# PAGE08_System_Power.net
KiCad netlist of a schematic drawn in Altium Designer
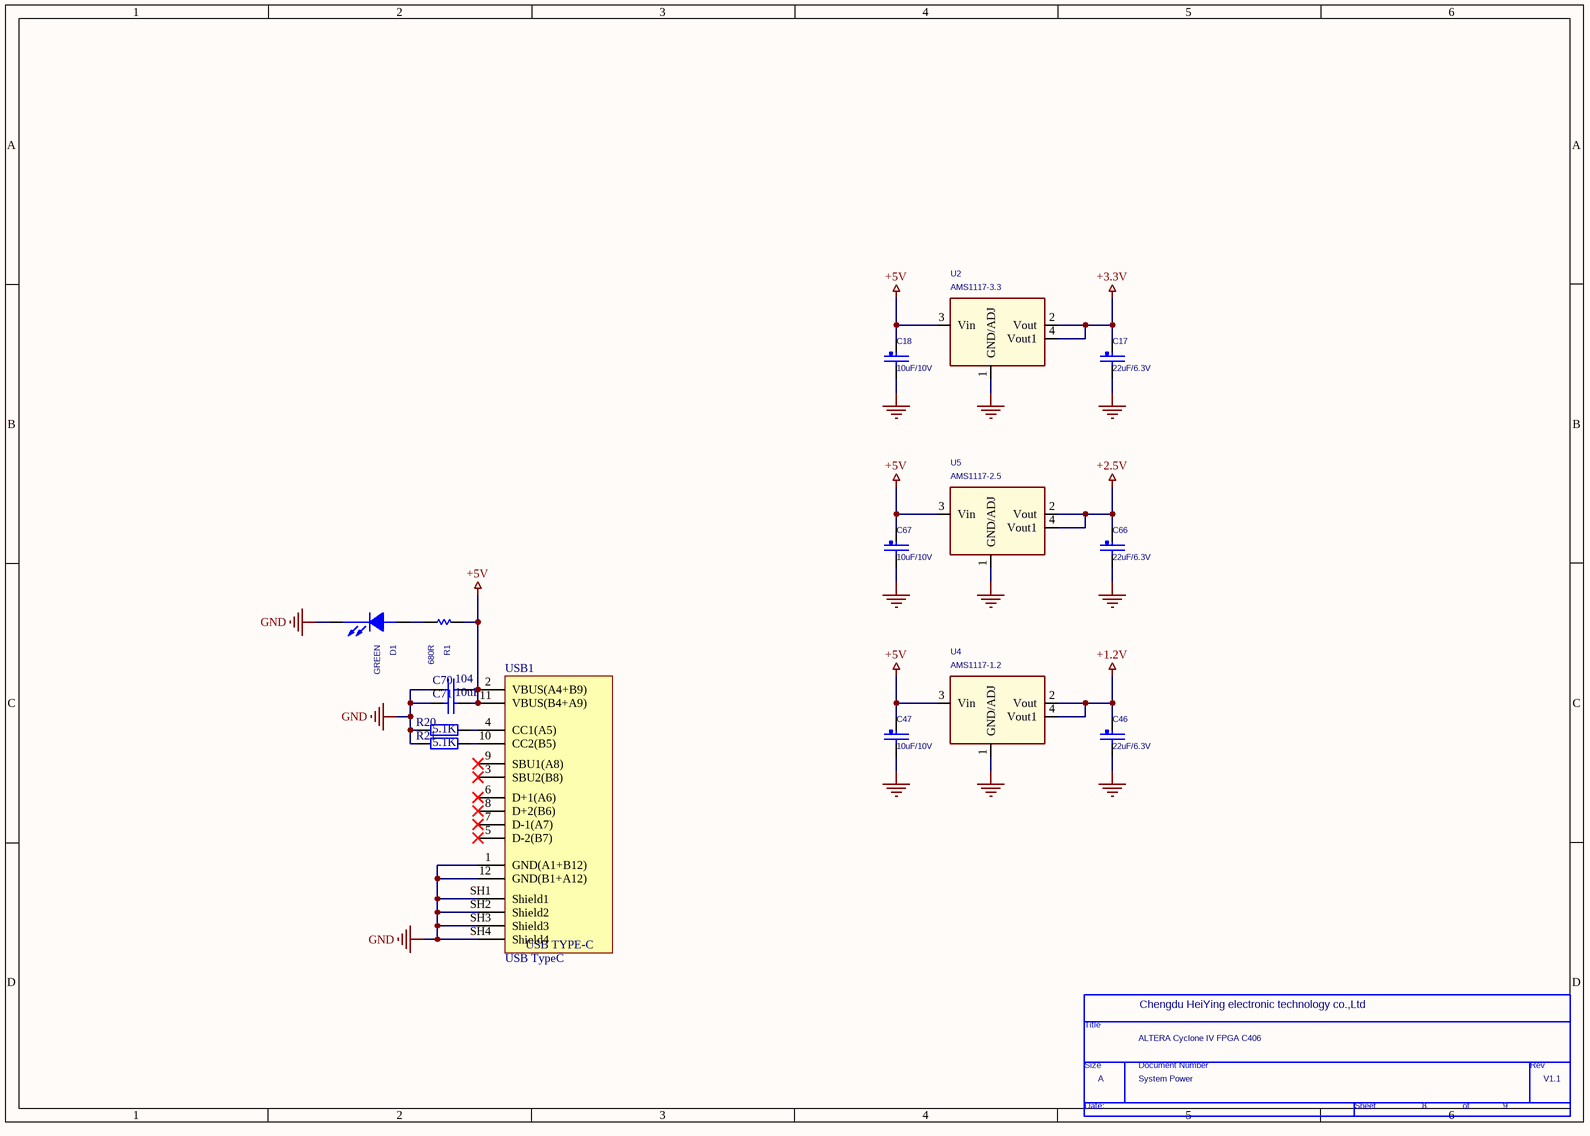
[diagram p0: PAGE08 System Power.SchDoc]

(export (version "E")
  (design (tool "Eeschema 10.0.6"))
  (components
    (comp (ref "C17")
      (value "22uF/6.3V")
      (description "Capacitor, 10u, 0805, X6S, 10%, 10V")
      (fields (field (name "TOLERANCE") "10%"))
      (libsource (lib "*") (part "CAP_NP"))
    )
    (comp (ref "C18")
      (value "10uF/10V")
      (description "CAP CER 22UF 16V 10%")
      (fields (field (name "TOLERANCE") "10%"))
      (libsource (lib "*") (part "CAP_NP"))
    )
    (comp (ref "C46")
      (value "22uF/6.3V")
      (description "Capacitor, 10u, 0805, X6S, 10%, 10V")
      (fields (field (name "TOLERANCE") "10%"))
      (libsource (lib "*") (part "CAP_NP"))
    )
    (comp (ref "C47")
      (value "10uF/10V")
      (description "CAP CER 22UF 16V 10%")
      (fields (field (name "TOLERANCE") "10%"))
      (libsource (lib "*") (part "CAP_NP"))
    )
    (comp (ref "C66")
      (value "22uF/6.3V")
      (description "Capacitor, 10u, 0805, X6S, 10%, 10V")
      (fields (field (name "TOLERANCE") "10%"))
      (libsource (lib "*") (part "CAP_NP"))
    )
    (comp (ref "C67")
      (value "10uF/10V")
      (description "CAP CER 22UF 16V 10%")
      (fields (field (name "TOLERANCE") "10%"))
      (libsource (lib "*") (part "CAP_NP"))
    )
    (comp (ref "C70")
      (value "104")
      (footprint "C 0603")
      (libsource (lib "ATK-DFPGL25G&50G_V1.3") (part "C-0603-SMD"))
    )
    (comp (ref "C71")
      (value "10uF")
      (footprint "C 0603")
      (libsource (lib "ATK-DFPGL25G&50G_V1.3") (part "C-0603-SMD"))
    )
    (comp (ref "D1") (value "GREEN") (libsource (lib "*") (part "LED")))
    (comp (ref "R1") (value "680R") (footprint "R 0603") (libsource (lib "*") (part "SMALL R1")))
    (comp (ref "R20")
      (value "5.1K")
      (footprint "R 0603")
      (description "电阻")
      (fields (field (name "版权归属") "正点原子"))
      (libsource (lib "ATK-DFPGL25G&50G_V1.3") (part "R"))
    )
    (comp (ref "R21")
      (value "5.1K")
      (footprint "R 0603")
      (description "电阻")
      (fields (field (name "版权归属") "正点原子"))
      (libsource (lib "ATK-DFPGL25G&50G_V1.3") (part "R"))
    )
    (comp (ref "U2") (value "AMS1117-3.3") (footprint "SOT-223") (libsource (lib "*") (part "AMS1117")))
    (comp (ref "U4") (value "AMS1117-1.2") (footprint "SOT-223") (libsource (lib "*") (part "AMS1117")))
    (comp (ref "U5") (value "AMS1117-2.5") (footprint "SOT-223") (libsource (lib "*") (part "AMS1117")))
    (comp (ref "USB1")
      (value "USB TypeC")
      (footprint "USB2.0-TYPE-C-16P")
      (description "12P TypeC 母座")
      (libsource (lib "ATK-DFPGL25G&50G_V1.3") (part "USB Type-C"))
    )
  )
  (nets
    (net (code "1") (name "+1.2V") (class "Default")
      (node (ref "C46") (pin "1") (pinfunction "1_1") (pintype "passive"))
      (node (ref "U4") (pin "2") (pinfunction "Vout_2") (pintype "power_in"))
      (node (ref "U4") (pin "4") (pinfunction "Vout1_4") (pintype "power_in"))
    )
    (net (code "2") (name "+2.5V") (class "Default")
      (node (ref "C66") (pin "1") (pinfunction "1_1") (pintype "passive"))
      (node (ref "U5") (pin "2") (pinfunction "Vout_2") (pintype "power_in"))
      (node (ref "U5") (pin "4") (pinfunction "Vout1_4") (pintype "power_in"))
    )
    (net (code "3") (name "+3.3V") (class "Default")
      (node (ref "C17") (pin "1") (pinfunction "1_1") (pintype "passive"))
      (node (ref "U2") (pin "2") (pinfunction "Vout_2") (pintype "power_in"))
      (node (ref "U2") (pin "4") (pinfunction "Vout1_4") (pintype "power_in"))
    )
    (net (code "4") (name "+5V") (class "Default")
      (node (ref "C18") (pin "1") (pinfunction "1_1") (pintype "passive"))
      (node (ref "C47") (pin "1") (pinfunction "1_1") (pintype "passive"))
      (node (ref "C67") (pin "1") (pinfunction "1_1") (pintype "passive"))
      (node (ref "C70") (pin "1") (pinfunction "1_1") (pintype "passive"))
      (node (ref "C71") (pin "1") (pinfunction "1_1") (pintype "passive"))
      (node (ref "R1") (pin "1") (pinfunction "1_1") (pintype "passive"))
      (node (ref "U2") (pin "3") (pinfunction "Vin_3") (pintype "power_in"))
      (node (ref "U4") (pin "3") (pinfunction "Vin_3") (pintype "power_in"))
      (node (ref "U5") (pin "3") (pinfunction "Vin_3") (pintype "power_in"))
      (node (ref "USB1") (pin "11") (pinfunction "VBUS(B4+A9)_11") (pintype "passive"))
      (node (ref "USB1") (pin "2") (pinfunction "VBUS(A4+B9)_2") (pintype "passive"))
    )
    (net (code "5") (name "GND") (class "Default")
      (node (ref "C17") (pin "2") (pinfunction "2_2") (pintype "passive"))
      (node (ref "C18") (pin "2") (pinfunction "2_2") (pintype "passive"))
      (node (ref "C46") (pin "2") (pinfunction "2_2") (pintype "passive"))
      (node (ref "C47") (pin "2") (pinfunction "2_2") (pintype "passive"))
      (node (ref "C66") (pin "2") (pinfunction "2_2") (pintype "passive"))
      (node (ref "C67") (pin "2") (pinfunction "2_2") (pintype "passive"))
      (node (ref "C70") (pin "2") (pinfunction "2_2") (pintype "passive"))
      (node (ref "C71") (pin "2") (pinfunction "2_2") (pintype "passive"))
      (node (ref "D1") (pin "2") (pinfunction "CATHODE_2") (pintype "passive"))
      (node (ref "R20") (pin "2") (pinfunction "2_2") (pintype "passive"))
      (node (ref "R21") (pin "2") (pinfunction "2_2") (pintype "passive"))
      (node (ref "U2") (pin "1") (pinfunction "GND/ADJ_1") (pintype "passive"))
      (node (ref "U4") (pin "1") (pinfunction "GND/ADJ_1") (pintype "passive"))
      (node (ref "U5") (pin "1") (pinfunction "GND/ADJ_1") (pintype "passive"))
      (node (ref "USB1") (pin "1") (pinfunction "GND(A1+B12)_1") (pintype "passive"))
      (node (ref "USB1") (pin "12") (pinfunction "GND(B1+A12)_12") (pintype "passive"))
      (node (ref "USB1") (pin "SH1") (pinfunction "Shield1_SH1") (pintype "passive"))
      (node (ref "USB1") (pin "SH2") (pinfunction "Shield2_SH2") (pintype "passive"))
      (node (ref "USB1") (pin "SH3") (pinfunction "Shield3_SH3") (pintype "passive"))
      (node (ref "USB1") (pin "SH4") (pinfunction "Shield4_SH4") (pintype "passive"))
    )
    (net (code "6") (name "Net-(D1-ANODE)") (class "Default")
      (node (ref "D1") (pin "1") (pinfunction "ANODE_1") (pintype "passive"))
      (node (ref "R1") (pin "2") (pinfunction "2_2") (pintype "passive"))
    )
    (net (code "7") (name "Net-(USB1-CC1(A5))") (class "Default")
      (node (ref "R20") (pin "1") (pinfunction "1_1") (pintype "passive"))
      (node (ref "USB1") (pin "4") (pinfunction "CC1(A5)_4") (pintype "passive"))
    )
    (net (code "8") (name "Net-(USB1-CC2(B5))") (class "Default")
      (node (ref "R21") (pin "1") (pinfunction "1_1") (pintype "passive"))
      (node (ref "USB1") (pin "10") (pinfunction "CC2(B5)_10") (pintype "passive"))
    )
    (net (code "9") (name "unconnected-(USB1-D+1(A6)-Pad6)") (class "Default")
      (node (ref "USB1") (pin "6") (pinfunction "D+1(A6)_6") (pintype "passive+no_connect"))
    )
    (net (code "10") (name "unconnected-(USB1-D+2(B6)-Pad8)") (class "Default")
      (node (ref "USB1") (pin "8") (pinfunction "D+2(B6)_8") (pintype "passive+no_connect"))
    )
    (net (code "11") (name "unconnected-(USB1-D-1(A7)-Pad7)") (class "Default")
      (node (ref "USB1") (pin "7") (pinfunction "D-1(A7)_7") (pintype "passive+no_connect"))
    )
    (net (code "12") (name "unconnected-(USB1-D-2(B7)-Pad5)") (class "Default")
      (node (ref "USB1") (pin "5") (pinfunction "D-2(B7)_5") (pintype "passive+no_connect"))
    )
    (net (code "13") (name "unconnected-(USB1-SBU1(A8)-Pad9)") (class "Default")
      (node (ref "USB1") (pin "9") (pinfunction "SBU1(A8)_9") (pintype "passive+no_connect"))
    )
    (net (code "14") (name "unconnected-(USB1-SBU2(B8)-Pad3)") (class "Default")
      (node (ref "USB1") (pin "3") (pinfunction "SBU2(B8)_3") (pintype "passive+no_connect"))
    )
  )
)
